# DK_MOTO.net
KiCad netlist of a schematic drawn in Altium Designer
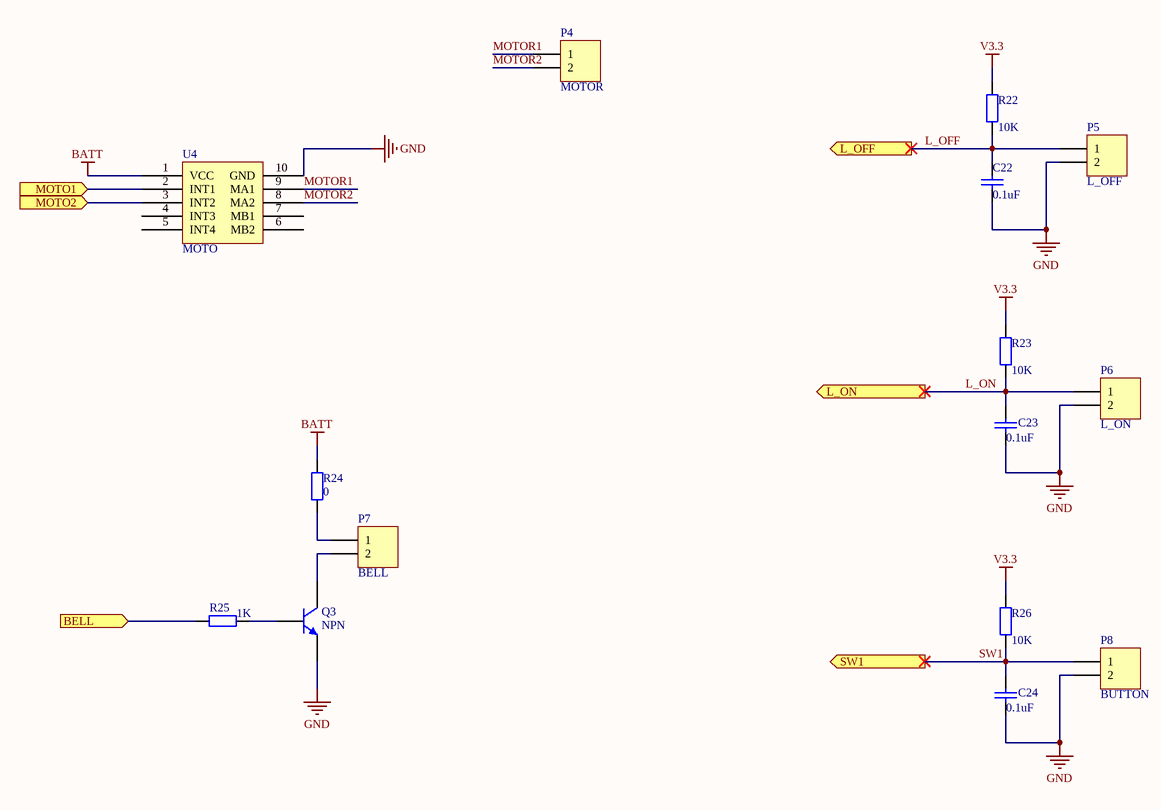
[diagram p0: DK_MOTO.SchDoc]

(export (version "E")
  (design (tool "Eeschema 10.0.6"))
  (components
    (comp (ref "C22")
      (value "0.1uF")
      (footprint "0603")
      (description "Capacitor")
      (fields (field (name "Comment") "Cap") (field (name "PUBLISHER") "Altium Limited"))
      (libsource (lib "Miscellaneous Devices") (part "Cap"))
    )
    (comp (ref "C23")
      (value "0.1uF")
      (footprint "0603")
      (description "Capacitor")
      (fields (field (name "Comment") "Cap") (field (name "PUBLISHER") "Altium Limited"))
      (libsource (lib "Miscellaneous Devices") (part "Cap"))
    )
    (comp (ref "C24")
      (value "0.1uF")
      (footprint "0603")
      (description "Capacitor")
      (fields (field (name "Comment") "Cap") (field (name "PUBLISHER") "Altium Limited"))
      (libsource (lib "Miscellaneous Devices") (part "Cap"))
    )
    (comp (ref "P4")
      (value "MOTOR")
      (footprint "COM2")
      (description "Header, 2-Pin")
      (fields (field (name "PUBLISHER") "Altium Limited"))
      (libsource (lib "Miscellaneous Connectors") (part "Header 2"))
    )
    (comp (ref "P5")
      (value "L_OFF")
      (footprint "COM2")
      (description "Header, 2-Pin")
      (fields (field (name "PUBLISHER") "Altium Limited"))
      (libsource (lib "Miscellaneous Connectors") (part "Header 2"))
    )
    (comp (ref "P6")
      (value "L_ON")
      (footprint "wzy:COM2")
      (description "Header, 2-Pin")
      (fields (field (name "PUBLISHER") "Altium Limited"))
      (libsource (lib "Miscellaneous Connectors") (part "Header 2"))
    )
    (comp (ref "P7")
      (value "BELL")
      (footprint "COM2")
      (description "Header, 2-Pin")
      (fields (field (name "PUBLISHER") "Altium Limited"))
      (libsource (lib "Miscellaneous Connectors") (part "Header 2"))
    )
    (comp (ref "P8")
      (value "BUTTON")
      (footprint "COM2")
      (description "Header, 2-Pin")
      (fields (field (name "PUBLISHER") "Altium Limited"))
      (libsource (lib "Miscellaneous Connectors") (part "Header 2"))
    )
    (comp (ref "Q3")
      (value "NPN")
      (footprint "SOT-23A")
      (description "NPN Bipolar Transistor")
      (fields (field (name "PUBLISHER") "Altium Limited"))
      (libsource (lib "Miscellaneous Devices") (part "NPN"))
    )
    (comp (ref "R22")
      (value "10K")
      (footprint "0603")
      (description "Resistor")
      (fields (field (name "Comment") "Res2") (field (name "PUBLISHER") "Altium Limited"))
      (libsource (lib "Miscellaneous Devices") (part "Res2"))
    )
    (comp (ref "R23")
      (value "10K")
      (footprint "0603")
      (description "Resistor")
      (fields (field (name "Comment") "Res2") (field (name "PUBLISHER") "Altium Limited"))
      (libsource (lib "Miscellaneous Devices") (part "Res2"))
    )
    (comp (ref "R24")
      (value "0")
      (footprint "0603")
      (description "Resistor")
      (fields (field (name "Comment") "Res2") (field (name "PUBLISHER") "Altium Limited"))
      (libsource (lib "Miscellaneous Devices") (part "Res2"))
    )
    (comp (ref "R25")
      (value "1K")
      (footprint "0603")
      (description "Resistor")
      (fields (field (name "Comment") "Res2") (field (name "PUBLISHER") "Altium Limited"))
      (libsource (lib "") (part "Res2_1"))
    )
    (comp (ref "R26")
      (value "10K")
      (footprint "0603")
      (description "Resistor")
      (fields (field (name "Comment") "Res2") (field (name "PUBLISHER") "Altium Limited"))
      (libsource (lib "Miscellaneous Devices") (part "Res2"))
    )
    (comp (ref "U4") (value "MOTO") (footprint "MOTO2") (libsource (lib "MOTO") (part "MOTO")))
  )
  (nets
    (net (code "1") (name "/BELL") (class "Default")
      (node (ref "R25") (pin "1") (pinfunction "1_1") (pintype "passive"))
    )
    (net (code "2") (name "/L_OFF") (class "Default")
      (node (ref "C22") (pin "2") (pinfunction "2_2") (pintype "passive"))
      (node (ref "P5") (pin "1") (pinfunction "1_1") (pintype "passive"))
      (node (ref "R22") (pin "1") (pinfunction "1_1") (pintype "passive"))
    )
    (net (code "3") (name "/L_ON") (class "Default")
      (node (ref "C23") (pin "2") (pinfunction "2_2") (pintype "passive"))
      (node (ref "P6") (pin "1") (pinfunction "1_1") (pintype "passive"))
      (node (ref "R23") (pin "1") (pinfunction "1_1") (pintype "passive"))
    )
    (net (code "4") (name "/MOTO1") (class "Default")
      (node (ref "U4") (pin "2") (pinfunction "INT1_2") (pintype "passive"))
    )
    (net (code "5") (name "/MOTO2") (class "Default")
      (node (ref "U4") (pin "3") (pinfunction "INT2_3") (pintype "passive"))
    )
    (net (code "6") (name "/MOTOR1") (class "Default")
      (node (ref "P4") (pin "1") (pinfunction "1_1") (pintype "passive"))
      (node (ref "U4") (pin "9") (pinfunction "MA1_9") (pintype "passive"))
    )
    (net (code "7") (name "/MOTOR2") (class "Default")
      (node (ref "P4") (pin "2") (pinfunction "2_2") (pintype "passive"))
      (node (ref "U4") (pin "8") (pinfunction "MA2_8") (pintype "passive"))
    )
    (net (code "8") (name "/SW1") (class "Default")
      (node (ref "C24") (pin "2") (pinfunction "2_2") (pintype "passive"))
      (node (ref "P8") (pin "1") (pinfunction "1_1") (pintype "passive"))
      (node (ref "R26") (pin "1") (pinfunction "1_1") (pintype "passive"))
    )
    (net (code "9") (name "BATT") (class "Default")
      (node (ref "R24") (pin "2") (pinfunction "2_2") (pintype "passive"))
      (node (ref "U4") (pin "1") (pinfunction "VCC_1") (pintype "passive"))
    )
    (net (code "10") (name "GND") (class "Default")
      (node (ref "C22") (pin "1") (pinfunction "1_1") (pintype "passive"))
      (node (ref "C23") (pin "1") (pinfunction "1_1") (pintype "passive"))
      (node (ref "C24") (pin "1") (pinfunction "1_1") (pintype "passive"))
      (node (ref "P5") (pin "2") (pinfunction "2_2") (pintype "passive"))
      (node (ref "P6") (pin "2") (pinfunction "2_2") (pintype "passive"))
      (node (ref "P8") (pin "2") (pinfunction "2_2") (pintype "passive"))
      (node (ref "Q3") (pin "3") (pinfunction "E_3") (pintype "passive"))
      (node (ref "U4") (pin "10") (pinfunction "GND_10") (pintype "passive"))
    )
    (net (code "11") (name "Net-(P7-Pad1)") (class "Default")
      (node (ref "P7") (pin "1") (pinfunction "1_1") (pintype "passive"))
      (node (ref "R24") (pin "1") (pinfunction "1_1") (pintype "passive"))
    )
    (net (code "12") (name "Net-(Q3-B)") (class "Default")
      (node (ref "Q3") (pin "2") (pinfunction "B_2") (pintype "passive"))
      (node (ref "R25") (pin "2") (pinfunction "2_2") (pintype "passive"))
    )
    (net (code "13") (name "Net-(Q3-C)") (class "Default")
      (node (ref "P7") (pin "2") (pinfunction "2_2") (pintype "passive"))
      (node (ref "Q3") (pin "1") (pinfunction "C_1") (pintype "passive"))
    )
    (net (code "14") (name "V3.3") (class "Default")
      (node (ref "R22") (pin "2") (pinfunction "2_2") (pintype "passive"))
      (node (ref "R23") (pin "2") (pinfunction "2_2") (pintype "passive"))
      (node (ref "R26") (pin "2") (pinfunction "2_2") (pintype "passive"))
    )
    (net (code "15") (name "unconnected-(U4-INT3-Pad4)") (class "Default")
      (node (ref "U4") (pin "4") (pinfunction "INT3_4") (pintype "passive"))
    )
    (net (code "16") (name "unconnected-(U4-INT4-Pad5)") (class "Default")
      (node (ref "U4") (pin "5") (pinfunction "INT4_5") (pintype "passive"))
    )
    (net (code "17") (name "unconnected-(U4-MB1-Pad7)") (class "Default")
      (node (ref "U4") (pin "7") (pinfunction "MB1_7") (pintype "passive"))
    )
    (net (code "18") (name "unconnected-(U4-MB2-Pad6)") (class "Default")
      (node (ref "U4") (pin "6") (pinfunction "MB2_6") (pintype "passive"))
    )
  )
)
